# robotic_arm_arduino_uno_shield_new.net
KiCad netlist of a schematic drawn in EAGLE
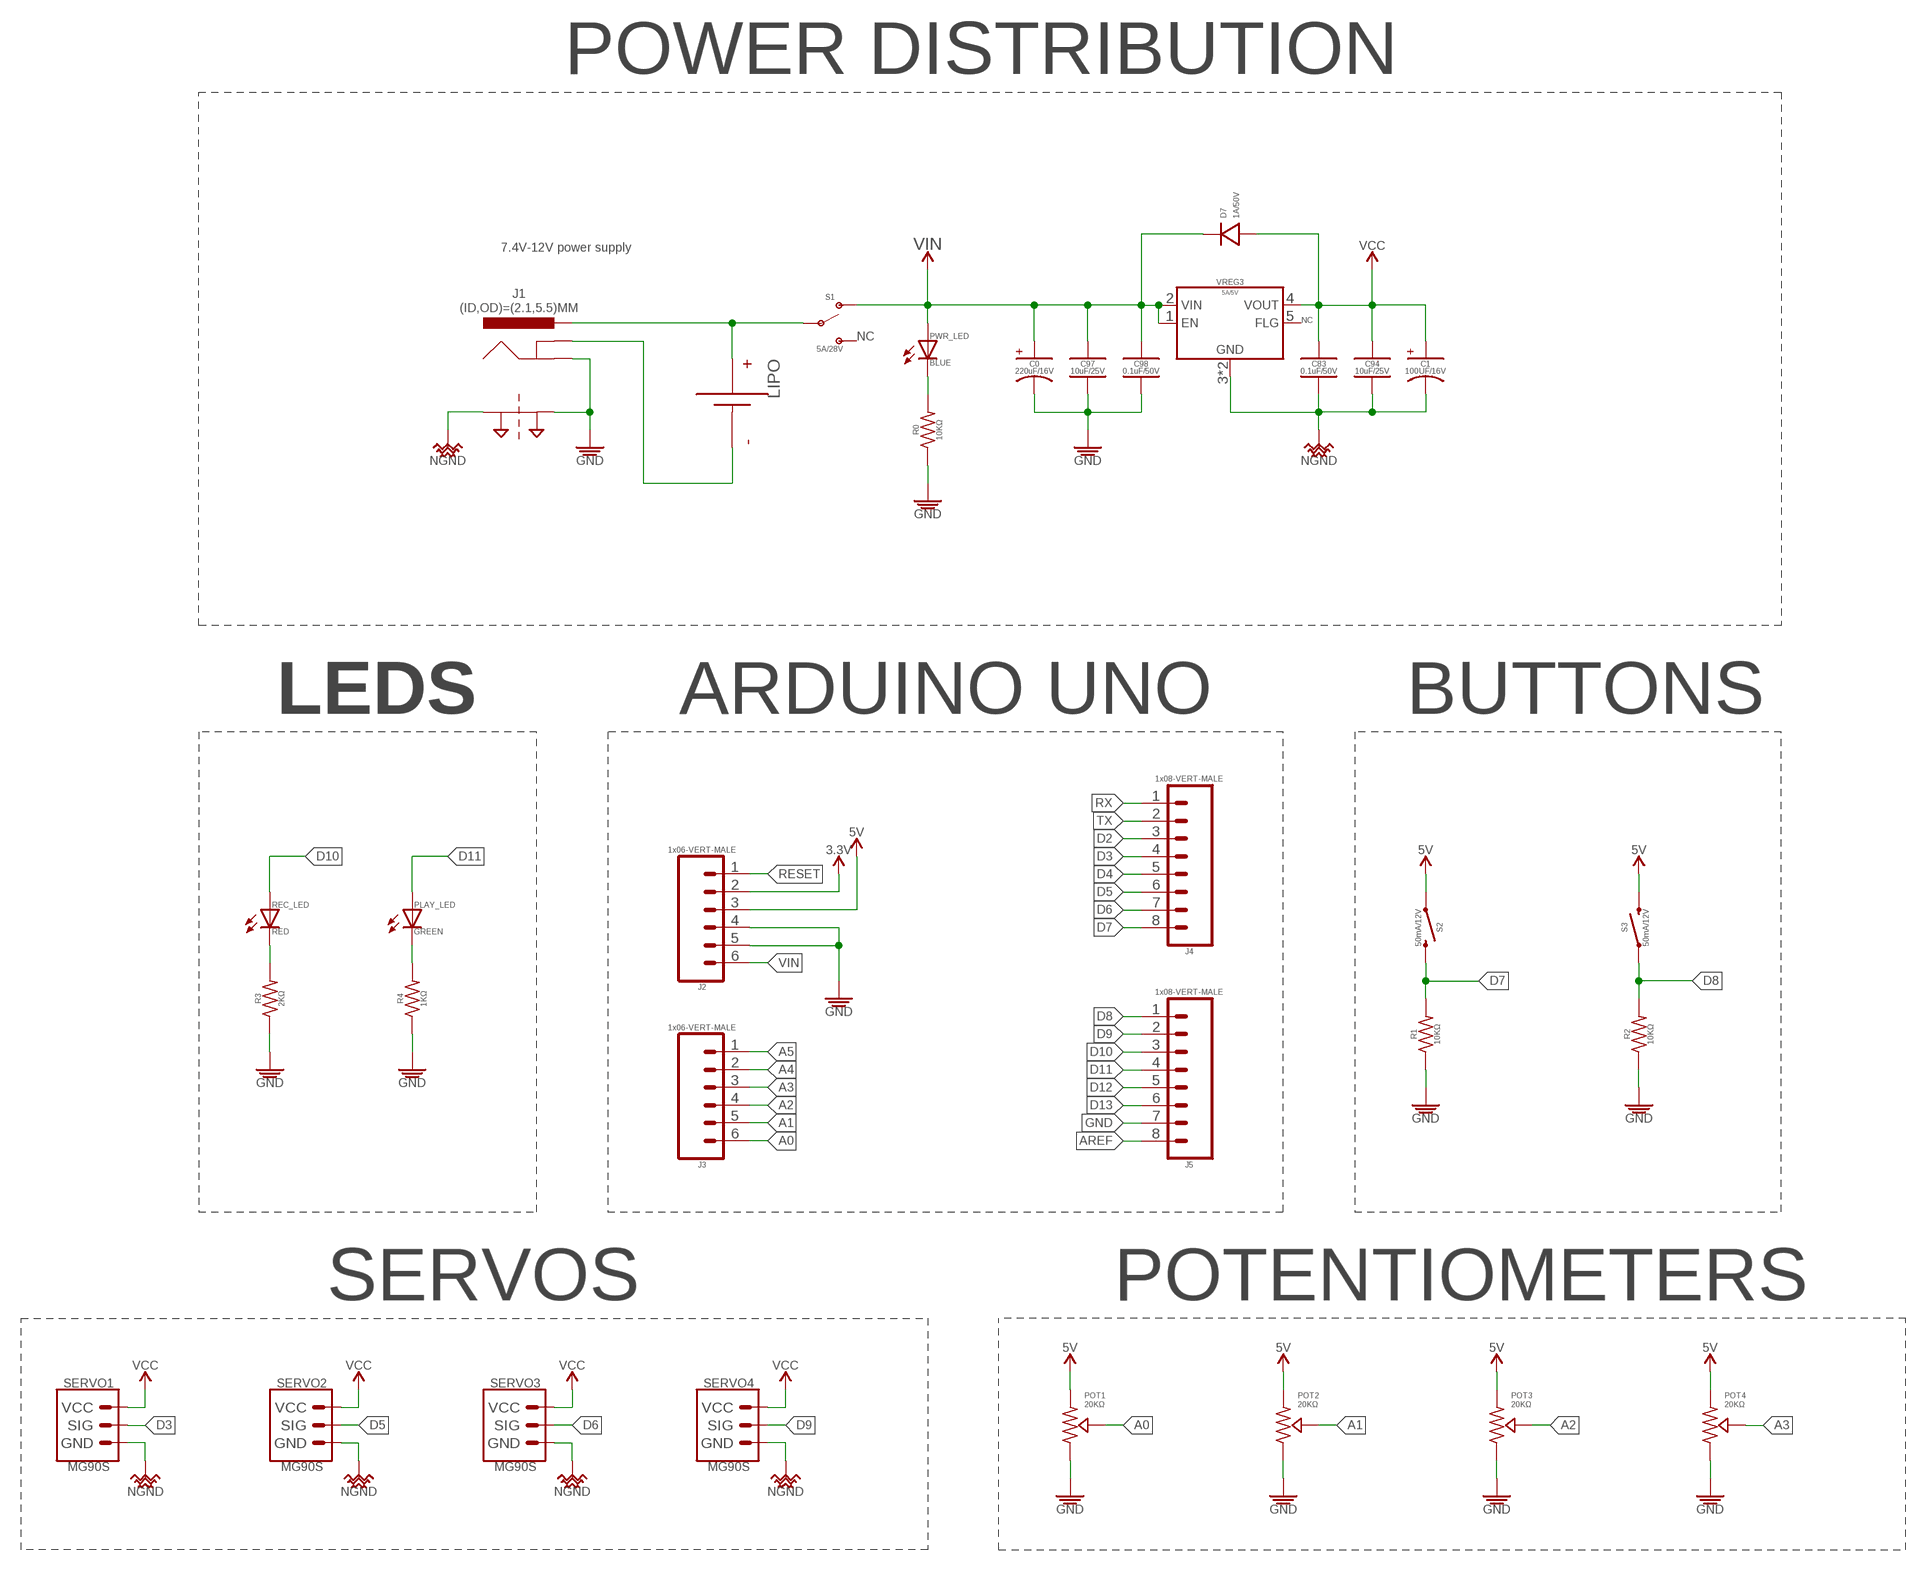
[diagram p0: schematic, sheet 1]

(export (version "E")
  (design (tool "Eeschema 10.0.6"))
  (components
    (comp (ref "C0")
      (value "220uF/16V")
      (footprint "eagle-import:CAP_POL_SMD_L6.6-W6.6")
      (fields
        (field (name "MFR") "Panasonic Electronic Components")
        (field (name "MPN") "EEE-FT1C221AP")
        (field (name "CREATOR") "MrSwirlyEyes")
      )
      (libsource (lib "eagle-import") (part "CAP_POLARIZED_ALUM-ELECTROLYTIC_SMD_220UF-16V-20%"))
    )
    (comp (ref "C1")
      (value "100UF/16V")
      (footprint "eagle-import:CAP_POL_SMD_L6.6-W6.6")
      (fields
        (field (name "MFR") "Panasonic Electronic Components")
        (field (name "MPN") "EEE-FK1C101P")
        (field (name "CREATOR") "MrSwirlyEyes")
      )
      (libsource (lib "eagle-import") (part "CAP_POLARIZED_ALUM-ELECTROLYTIC_SMD_100UF-16V-20%"))
    )
    (comp (ref "C83")
      (value "0.1uF/50V")
      (footprint "eagle-import:CAP_CER_SMD-805")
      (fields
        (field (name "MFR") "Murata Electronics North America")
        (field (name "MPN") "GRM21BR71H104KA01L")
        (field (name "CREATOR") "MrSwirlyEyes")
      )
      (libsource (lib "eagle-import") (part "CAP_CERAMIC_SMD-805_0.1UF-50V-10%"))
    )
    (comp (ref "C94")
      (value "10uF/25V")
      (footprint "eagle-import:CAP_CER_SMD-805")
      (fields
        (field (name "MFR") "Murata Electronics North America")
        (field (name "MPN") "GRM21BR61E106KA73L")
        (field (name "CREATOR") "MrSwirlyEyes")
      )
      (libsource (lib "eagle-import") (part "CAP_CERAMIC_SMD-805_10UF-25V-10%"))
    )
    (comp (ref "C97")
      (value "10uF/25V")
      (footprint "eagle-import:CAP_CER_SMD-805")
      (fields
        (field (name "MFR") "Murata Electronics North America")
        (field (name "MPN") "GRM21BR61E106KA73L")
        (field (name "CREATOR") "MrSwirlyEyes")
      )
      (libsource (lib "eagle-import") (part "CAP_CERAMIC_SMD-805_10UF-25V-10%"))
    )
    (comp (ref "C98")
      (value "0.1uF/50V")
      (footprint "eagle-import:CAP_CER_SMD-805")
      (fields
        (field (name "MFR") "Murata Electronics North America")
        (field (name "MPN") "GRM21BR71H104KA01L")
        (field (name "CREATOR") "MrSwirlyEyes")
      )
      (libsource (lib "eagle-import") (part "CAP_CERAMIC_SMD-805_0.1UF-50V-10%"))
    )
    (comp (ref "D7")
      (value "1A/50V")
      (footprint "eagle-import:DIODE_SMD_1A-50V-SOD123F")
      (fields
        (field (name "MFR") "Comchip Technology")
        (field (name "MPN") "CGRKM4001-HF")
        (field (name "CREATOR") "MrSwirlyEyes")
      )
      (libsource (lib "eagle-import") (part "DIODE_GEN-PURPSMD_GP_1A-50V-SOD123F"))
    )
    (comp (ref "J1")
      (value "(ID,OD)=(2.1,5.5)MM")
      (footprint "eagle-import:POWER_JACK_SLOT_ID2.1MM-OD5.5MM")
      (fields
        (field (name "MFR") "MPD (Memory Protection Devices)")
        (field (name "MPN") "EJ508A")
        (field (name "CREATOR") "MrSwirlyEyes")
      )
      (libsource (lib "eagle-import") (part "POWER_JACK-BARREL_ID2.1MM-OD5.5MM"))
    )
    (comp (ref "J2")
      (value "1x06-VERT-MALE")
      (footprint "eagle-import:1X06-VERT-MALE")
      (fields
        (field (name "MFR") "Sullins Connector Solutions")
        (field (name "MPN") "PEC06SAAN")
        (field (name "CREATOR") "MrSwirlyEyes")
      )
      (libsource (lib "eagle-import") (part "1X06VERT-MALE"))
    )
    (comp (ref "J3")
      (value "1x06-VERT-MALE")
      (footprint "eagle-import:1X06-VERT-MALE")
      (fields
        (field (name "MFR") "Sullins Connector Solutions")
        (field (name "MPN") "PEC06SAAN")
        (field (name "CREATOR") "MrSwirlyEyes")
      )
      (libsource (lib "eagle-import") (part "1X06VERT-MALE"))
    )
    (comp (ref "J4")
      (value "1x08-VERT-MALE")
      (footprint "eagle-import:1X08-VERT-MALE")
      (fields
        (field (name "MFR") "Sullins Connector Solutions")
        (field (name "MPN") "PEC08SAAN")
        (field (name "CREATOR") "MrSwirlyEyes")
      )
      (libsource (lib "eagle-import") (part "1X08VERT-MALE"))
    )
    (comp (ref "J5")
      (value "1x08-VERT-MALE")
      (footprint "eagle-import:1X08-VERT-MALE")
      (fields
        (field (name "MFR") "Sullins Connector Solutions")
        (field (name "MPN") "PEC08SAAN")
        (field (name "CREATOR") "MrSwirlyEyes")
      )
      (libsource (lib "eagle-import") (part "1X08VERT-MALE"))
    )
    (comp (ref "LIPO")
      (value "BATTERYPTH_HOLES")
      (footprint "eagle-import:DUAL_PTH_PADS")
      (libsource (lib "eagle-import") (part "BATTERYPTH_HOLES"))
    )
    (comp (ref "PLAY_LED")
      (value "GREEN")
      (footprint "eagle-import:LED_SMD-805_")
      (fields
        (field (name "MFR") "Lite-On Inc.")
        (field (name "MPN") "LTST-C170KGKT")
        (field (name "CREATOR") "MrSwirlyEyes")
      )
      (libsource (lib "eagle-import") (part "LED_SMD-805_DISCRETE_GREEN"))
    )
    (comp (ref "POT1")
      (value "20KΩ")
      (footprint "eagle-import:CONNECTOR_POTENTIOMETER_NO-MARKINGS_FEMALE-HEADER")
      (fields
        (field (name "MFR") "Bourns Inc.")
        (field (name "MPN") "PDB181-K420K-203B")
        (field (name "CREATOR") "MrSwirlyEyes")
      )
      (libsource (lib "eagle-import") (part "POTENTIOMETERNO-MARKINGS_VERT-FEMALE"))
    )
    (comp (ref "POT2")
      (value "20KΩ")
      (footprint "eagle-import:CONNECTOR_POTENTIOMETER_NO-MARKINGS_FEMALE-HEADER")
      (fields
        (field (name "MFR") "Bourns Inc.")
        (field (name "MPN") "PDB181-K420K-203B")
        (field (name "CREATOR") "MrSwirlyEyes")
      )
      (libsource (lib "eagle-import") (part "POTENTIOMETERNO-MARKINGS_VERT-FEMALE"))
    )
    (comp (ref "POT3")
      (value "20KΩ")
      (footprint "eagle-import:CONNECTOR_POTENTIOMETER_NO-MARKINGS_FEMALE-HEADER")
      (fields
        (field (name "MFR") "Bourns Inc.")
        (field (name "MPN") "PDB181-K420K-203B")
        (field (name "CREATOR") "MrSwirlyEyes")
      )
      (libsource (lib "eagle-import") (part "POTENTIOMETERNO-MARKINGS_VERT-FEMALE"))
    )
    (comp (ref "POT4")
      (value "20KΩ")
      (footprint "eagle-import:CONNECTOR_POTENTIOMETER_NO-MARKINGS_FEMALE-HEADER")
      (fields
        (field (name "MFR") "Bourns Inc.")
        (field (name "MPN") "PDB181-K420K-203B")
        (field (name "CREATOR") "MrSwirlyEyes")
      )
      (libsource (lib "eagle-import") (part "POTENTIOMETERNO-MARKINGS_VERT-FEMALE"))
    )
    (comp (ref "PWR_LED")
      (value "BLUE")
      (footprint "eagle-import:LED_SMD-805_")
      (fields
        (field (name "MFR") "Lite-On Inc.")
        (field (name "MPN") "LTST-C170TBKT")
        (field (name "CREATOR") "MrSwirlyEyes")
      )
      (libsource (lib "eagle-import") (part "LED_SMD-805_DISCRETE_BLUE"))
    )
    (comp (ref "R0")
      (value "10KΩ")
      (footprint "eagle-import:RESISTOR_SMD-805")
      (fields
        (field (name "MFR") "Yageo")
        (field (name "MPN") "RC0805JR-0710KL")
        (field (name "CREATOR") "Kenmei")
      )
      (libsource (lib "eagle-import") (part "RESISTORSMD-0805_1/8W_10K_5%"))
    )
    (comp (ref "R1")
      (value "10KΩ")
      (footprint "eagle-import:RESISTOR_SMD-805")
      (fields
        (field (name "MFR") "Yageo")
        (field (name "MPN") "RC0805JR-0710KL")
        (field (name "CREATOR") "Kenmei")
      )
      (libsource (lib "eagle-import") (part "RESISTORSMD-0805_1/8W_10K_5%"))
    )
    (comp (ref "R2")
      (value "10KΩ")
      (footprint "eagle-import:RESISTOR_SMD-805")
      (fields
        (field (name "MFR") "Yageo")
        (field (name "MPN") "RC0805JR-0710KL")
        (field (name "CREATOR") "Kenmei")
      )
      (libsource (lib "eagle-import") (part "RESISTORSMD-0805_1/8W_10K_5%"))
    )
    (comp (ref "R3")
      (value "2KΩ")
      (footprint "eagle-import:RESISTOR_SMD-805")
      (fields
        (field (name "MFR") "Yageo")
        (field (name "MPN") "RC0805JR-072KL")
        (field (name "CREATOR") "MrSwirlyEyes")
      )
      (libsource (lib "eagle-import") (part "RESISTORSMD-0805_1/8W_2K_5%"))
    )
    (comp (ref "R4")
      (value "1KΩ")
      (footprint "eagle-import:RESISTOR_SMD-805")
      (fields
        (field (name "MFR") "Yageo")
        (field (name "MPN") "RC0805JR-071KL ")
        (field (name "CREATOR") "Kenmei")
      )
      (libsource (lib "eagle-import") (part "RESISTORSMD-0805_1/8W_1K_5%"))
    )
    (comp (ref "REC_LED")
      (value "RED")
      (footprint "eagle-import:LED_SMD-805_")
      (fields
        (field (name "MFR") "Lite-On Inc.")
        (field (name "MPN") "LTST-C170KRKT")
        (field (name "CREATOR") "MrSwirlyEyes")
      )
      (libsource (lib "eagle-import") (part "LED_SMD-805_DISCRETE_RED"))
    )
    (comp (ref "S1")
      (value "5A/28V")
      (footprint "eagle-import:SW-SLIDE_SPDT_5A-28V_13L-7W")
      (fields
        (field (name "MFR") "E-Switch")
        (field (name "MPN") "100SP1T1B4M2QE")
        (field (name "CREATOR") "MrSwirlyEyes")
      )
      (libsource (lib "eagle-import") (part "SWITCH_SPDT5A-28V_13L-7W"))
    )
    (comp (ref "S2")
      (value "50mA/12V")
      (footprint "eagle-import:SPST-PTH-12MM")
      (fields (field (name "CREATOR") "MrSwirlyEyes"))
      (libsource (lib "eagle-import") (part "SWITCH_MOMENTARY_SPSTSPST-PTH-L12-W12-H7.2"))
    )
    (comp (ref "S3")
      (value "50mA/12V")
      (footprint "eagle-import:SPST-PTH-12MM")
      (fields (field (name "CREATOR") "MrSwirlyEyes"))
      (libsource (lib "eagle-import") (part "SWITCH_MOMENTARY_SPSTSPST-PTH-L12-W12-H7.2"))
    )
    (comp (ref "SERVO1")
      (value "MG90S")
      (footprint "eagle-import:CONNECTOR_SERVO_NO-MARKINGS")
      (fields (field (name "MFR") "TowerPro") (field (name "CREATOR") "MrSwirlyEyes"))
      (libsource (lib "eagle-import") (part "SERVOMG90S_NO-MARKINGS"))
    )
    (comp (ref "SERVO2")
      (value "MG90S")
      (footprint "eagle-import:CONNECTOR_SERVO_NO-MARKINGS")
      (fields (field (name "MFR") "TowerPro") (field (name "CREATOR") "MrSwirlyEyes"))
      (libsource (lib "eagle-import") (part "SERVOMG90S_NO-MARKINGS"))
    )
    (comp (ref "SERVO3")
      (value "MG90S")
      (footprint "eagle-import:CONNECTOR_SERVO_NO-MARKINGS")
      (fields (field (name "MFR") "TowerPro") (field (name "CREATOR") "MrSwirlyEyes"))
      (libsource (lib "eagle-import") (part "SERVOMG90S_NO-MARKINGS"))
    )
    (comp (ref "SERVO4")
      (value "MG90S")
      (footprint "eagle-import:CONNECTOR_SERVO_NO-MARKINGS")
      (fields (field (name "MFR") "TowerPro") (field (name "CREATOR") "MrSwirlyEyes"))
      (libsource (lib "eagle-import") (part "SERVOMG90S_NO-MARKINGS"))
    )
    (comp (ref "SUPPLY14")
      (value "2PT_GND_TIE")
      (footprint "eagle-import:2PT_GND_TIE")
      (libsource (lib "eagle-import") (part "2PT_GND_TIE"))
    )
    (comp (ref "VREG3")
      (value "5A/5V")
      (footprint "eagle-import:TO-263-5")
      (fields
        (field (name "MFR") "Microchip Technology")
        (field (name "MPN") "MIC29501-5.0WU")
        (field (name "CREATOR") "MrSwirlyEyes")
      )
      (libsource (lib "eagle-import") (part "VREG_MIC29501-5.0_LINEAR_ULDO_5A-5VMIC29501-5.0_5A-5V"))
    )
  )
  (nets
    (net (code "1") (name "3.3V") (class "Default")
      (node (ref "J2") (pin "2") (pinfunction "2_2") (pintype "passive"))
    )
    (net (code "2") (name "5V") (class "Default")
      (node (ref "J2") (pin "3") (pinfunction "3_3") (pintype "passive"))
      (node (ref "POT1") (pin "CCW") (pinfunction "CCW_CCW") (pintype "passive"))
      (node (ref "POT2") (pin "CCW") (pinfunction "CCW_CCW") (pintype "passive"))
      (node (ref "POT3") (pin "CCW") (pinfunction "CCW_CCW") (pintype "passive"))
      (node (ref "POT4") (pin "CCW") (pinfunction "CCW_CCW") (pintype "passive"))
      (node (ref "S2") (pin "1") (pinfunction "1_1") (pintype "passive"))
      (node (ref "S3") (pin "3") (pinfunction "2_3") (pintype "passive"))
    )
    (net (code "3") (name "A0") (class "Default")
      (node (ref "J3") (pin "6") (pinfunction "6_6") (pintype "passive"))
      (node (ref "POT1") (pin "S") (pinfunction "S_S") (pintype "passive"))
    )
    (net (code "4") (name "A1") (class "Default")
      (node (ref "J3") (pin "5") (pinfunction "5_5") (pintype "passive"))
      (node (ref "POT2") (pin "S") (pinfunction "S_S") (pintype "passive"))
    )
    (net (code "5") (name "A2") (class "Default")
      (node (ref "J3") (pin "4") (pinfunction "4_4") (pintype "passive"))
      (node (ref "POT3") (pin "S") (pinfunction "S_S") (pintype "passive"))
    )
    (net (code "6") (name "A3") (class "Default")
      (node (ref "J3") (pin "3") (pinfunction "3_3") (pintype "passive"))
      (node (ref "POT4") (pin "S") (pinfunction "S_S") (pintype "passive"))
    )
    (net (code "7") (name "A4") (class "Default")
      (node (ref "J3") (pin "2") (pinfunction "2_2") (pintype "passive"))
    )
    (net (code "8") (name "A5") (class "Default")
      (node (ref "J3") (pin "1") (pinfunction "1_1") (pintype "passive"))
    )
    (net (code "9") (name "AREF") (class "Default")
      (node (ref "J5") (pin "8") (pinfunction "8_8") (pintype "passive"))
    )
    (net (code "10") (name "D2") (class "Default")
      (node (ref "J4") (pin "3") (pinfunction "3_3") (pintype "passive"))
    )
    (net (code "11") (name "D3") (class "Default")
      (node (ref "J4") (pin "4") (pinfunction "4_4") (pintype "passive"))
      (node (ref "SERVO1") (pin "1") (pinfunction "SIG_1") (pintype "passive"))
    )
    (net (code "12") (name "D4") (class "Default")
      (node (ref "J4") (pin "5") (pinfunction "5_5") (pintype "passive"))
    )
    (net (code "13") (name "D5") (class "Default")
      (node (ref "J4") (pin "6") (pinfunction "6_6") (pintype "passive"))
      (node (ref "SERVO2") (pin "1") (pinfunction "SIG_1") (pintype "passive"))
    )
    (net (code "14") (name "D6") (class "Default")
      (node (ref "J4") (pin "7") (pinfunction "7_7") (pintype "passive"))
      (node (ref "SERVO3") (pin "1") (pinfunction "SIG_1") (pintype "passive"))
    )
    (net (code "15") (name "D7") (class "Default")
      (node (ref "J4") (pin "8") (pinfunction "8_8") (pintype "passive"))
      (node (ref "R1") (pin "2") (pinfunction "2_2") (pintype "passive"))
      (node (ref "S2") (pin "3") (pinfunction "2_3") (pintype "passive"))
    )
    (net (code "16") (name "D8") (class "Default")
      (node (ref "J5") (pin "1") (pinfunction "1_1") (pintype "passive"))
      (node (ref "R2") (pin "2") (pinfunction "2_2") (pintype "passive"))
      (node (ref "S3") (pin "1") (pinfunction "1_1") (pintype "passive"))
    )
    (net (code "17") (name "D9") (class "Default")
      (node (ref "J5") (pin "2") (pinfunction "2_2") (pintype "passive"))
      (node (ref "SERVO4") (pin "1") (pinfunction "SIG_1") (pintype "passive"))
    )
    (net (code "18") (name "D10") (class "Default")
      (node (ref "J5") (pin "3") (pinfunction "3_3") (pintype "passive"))
      (node (ref "REC_LED") (pin "A") (pinfunction "A_A") (pintype "passive"))
    )
    (net (code "19") (name "D11") (class "Default")
      (node (ref "J5") (pin "4") (pinfunction "4_4") (pintype "passive"))
      (node (ref "PLAY_LED") (pin "A") (pinfunction "A_A") (pintype "passive"))
    )
    (net (code "20") (name "D12") (class "Default")
      (node (ref "J5") (pin "5") (pinfunction "5_5") (pintype "passive"))
    )
    (net (code "21") (name "D13") (class "Default")
      (node (ref "J5") (pin "6") (pinfunction "6_6") (pintype "passive"))
    )
    (net (code "22") (name "GND") (class "Default")
      (node (ref "C0") (pin "K") (pinfunction "K_K") (pintype "passive"))
      (node (ref "C97") (pin "2") (pinfunction "2_2") (pintype "passive"))
      (node (ref "C98") (pin "2") (pinfunction "2_2") (pintype "passive"))
      (node (ref "J1") (pin "GND@1") (pinfunction "GND_GND@1") (pintype "bidirectional"))
      (node (ref "J2") (pin "4") (pinfunction "4_4") (pintype "passive"))
      (node (ref "J2") (pin "5") (pinfunction "5_5") (pintype "passive"))
      (node (ref "J5") (pin "7") (pinfunction "7_7") (pintype "passive"))
      (node (ref "POT1") (pin "CW") (pinfunction "CW_CW") (pintype "passive"))
      (node (ref "POT2") (pin "CW") (pinfunction "CW_CW") (pintype "passive"))
      (node (ref "POT3") (pin "CW") (pinfunction "CW_CW") (pintype "passive"))
      (node (ref "POT4") (pin "CW") (pinfunction "CW_CW") (pintype "passive"))
      (node (ref "R0") (pin "1") (pinfunction "1_1") (pintype "passive"))
      (node (ref "R1") (pin "1") (pinfunction "1_1") (pintype "passive"))
      (node (ref "R2") (pin "1") (pinfunction "1_1") (pintype "passive"))
      (node (ref "R3") (pin "1") (pinfunction "1_1") (pintype "passive"))
      (node (ref "R4") (pin "1") (pinfunction "1_1") (pintype "passive"))
      (node (ref "SUPPLY14") (pin "P$2") (pinfunction "P$2_P$2") (pintype "bidirectional"))
    )
    (net (code "23") (name "NGND") (class "Default")
      (node (ref "C1") (pin "K") (pinfunction "K_K") (pintype "passive"))
      (node (ref "C83") (pin "2") (pinfunction "2_2") (pintype "passive"))
      (node (ref "C94") (pin "2") (pinfunction "2_2") (pintype "passive"))
      (node (ref "SERVO1") (pin "3") (pinfunction "GND_3") (pintype "passive"))
      (node (ref "SERVO2") (pin "3") (pinfunction "GND_3") (pintype "passive"))
      (node (ref "SERVO3") (pin "3") (pinfunction "GND_3") (pintype "passive"))
      (node (ref "SERVO4") (pin "3") (pinfunction "GND_3") (pintype "passive"))
      (node (ref "SUPPLY14") (pin "P$1") (pinfunction "P$1_P$1") (pintype "bidirectional"))
      (node (ref "VREG3") (pin "3") (pinfunction "GND_3") (pintype "bidirectional"))
      (node (ref "VREG3") (pin "TAB") (pinfunction "GND_TAB") (pintype "bidirectional"))
    )
    (net (code "24") (name "Net-(LIPO-N)") (class "Default")
      (node (ref "J1") (pin "GND@2") (pinfunction "GND_GND@2") (pintype "bidirectional"))
      (node (ref "LIPO") (pin "-") (pinfunction "N_-") (pintype "bidirectional"))
    )
    (net (code "25") (name "Net-(LIPO-P)") (class "Default")
      (node (ref "J1") (pin "PWR") (pinfunction "PWR_PWR") (pintype "bidirectional"))
      (node (ref "LIPO") (pin "+") (pinfunction "P_+") (pintype "bidirectional"))
      (node (ref "S1") (pin "P$2") (pinfunction "P_P$2") (pintype "passive"))
    )
    (net (code "26") (name "Net-(PLAY_LED-PadK)") (class "Default")
      (node (ref "PLAY_LED") (pin "K") (pinfunction "K_K") (pintype "passive"))
      (node (ref "R4") (pin "2") (pinfunction "2_2") (pintype "passive"))
    )
    (net (code "27") (name "Net-(PWR_LED-PadK)") (class "Default")
      (node (ref "PWR_LED") (pin "K") (pinfunction "K_K") (pintype "passive"))
      (node (ref "R0") (pin "2") (pinfunction "2_2") (pintype "passive"))
    )
    (net (code "28") (name "Net-(R3-Pad2)") (class "Default")
      (node (ref "R3") (pin "2") (pinfunction "2_2") (pintype "passive"))
      (node (ref "REC_LED") (pin "K") (pinfunction "K_K") (pintype "passive"))
    )
    (net (code "29") (name "RESET") (class "Default")
      (node (ref "J2") (pin "1") (pinfunction "1_1") (pintype "passive"))
    )
    (net (code "30") (name "RX") (class "Default")
      (node (ref "J4") (pin "1") (pinfunction "1_1") (pintype "passive"))
    )
    (net (code "31") (name "TX") (class "Default")
      (node (ref "J4") (pin "2") (pinfunction "2_2") (pintype "passive"))
    )
    (net (code "32") (name "VCC") (class "Default")
      (node (ref "C1") (pin "A") (pinfunction "A_A") (pintype "passive"))
      (node (ref "C83") (pin "1") (pinfunction "1_1") (pintype "passive"))
      (node (ref "C94") (pin "1") (pinfunction "1_1") (pintype "passive"))
      (node (ref "D7") (pin "A") (pinfunction "A_A") (pintype "passive"))
      (node (ref "SERVO1") (pin "2") (pinfunction "VCC_2") (pintype "passive"))
      (node (ref "SERVO2") (pin "2") (pinfunction "VCC_2") (pintype "passive"))
      (node (ref "SERVO3") (pin "2") (pinfunction "VCC_2") (pintype "passive"))
      (node (ref "SERVO4") (pin "2") (pinfunction "VCC_2") (pintype "passive"))
      (node (ref "VREG3") (pin "4") (pinfunction "VOUT_4") (pintype "bidirectional"))
    )
    (net (code "33") (name "VIN") (class "Default")
      (node (ref "C0") (pin "A") (pinfunction "A_A") (pintype "passive"))
      (node (ref "C97") (pin "1") (pinfunction "1_1") (pintype "passive"))
      (node (ref "C98") (pin "1") (pinfunction "1_1") (pintype "passive"))
      (node (ref "D7") (pin "K") (pinfunction "K_K") (pintype "passive"))
      (node (ref "J2") (pin "6") (pinfunction "6_6") (pintype "passive"))
      (node (ref "PWR_LED") (pin "A") (pinfunction "A_A") (pintype "passive"))
      (node (ref "S1") (pin "P$1") (pinfunction "S1_P$1") (pintype "passive"))
      (node (ref "VREG3") (pin "1") (pinfunction "EN_1") (pintype "bidirectional"))
      (node (ref "VREG3") (pin "2") (pinfunction "VIN_2") (pintype "bidirectional"))
    )
    (net (code "34") (name "unconnected-(S1-S2-PadP$3)") (class "Default")
      (node (ref "S1") (pin "P$3") (pinfunction "S2_P$3") (pintype "passive"))
    )
    (net (code "35") (name "unconnected-(VREG3-FLG-Pad5)") (class "Default")
      (node (ref "VREG3") (pin "5") (pinfunction "FLG_5") (pintype "bidirectional"))
    )
  )
)
